# CH32F203CBT6-R0.net
KiCad netlist of a schematic drawn in Altium Designer
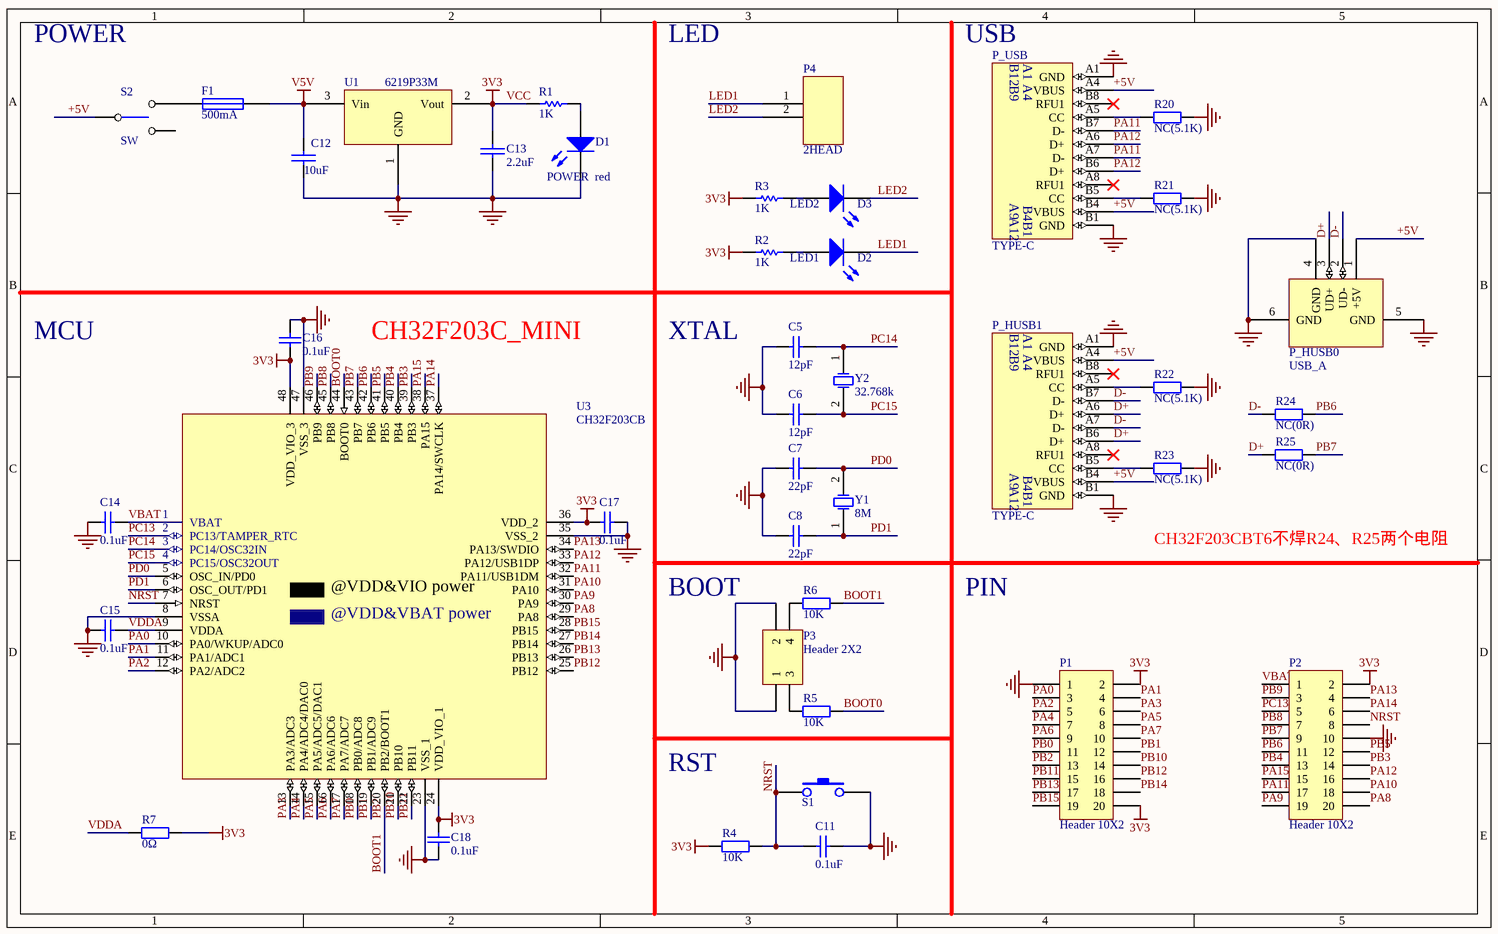
[diagram p0: CH32F203CBT6-R0.SchDoc]

(export (version "E")
  (design (tool "Eeschema 10.0.6"))
  (components
    (comp (ref "C5")
      (value "12pF")
      (footprint "0603")
      (description "Capacitor")
      (fields (field (name "PUBLISHER") "Altium Limited"))
      (libsource (lib "*") (part "Cap"))
    )
    (comp (ref "C6")
      (value "12pF")
      (footprint "0603")
      (description "Capacitor")
      (fields (field (name "PUBLISHER") "Altium Limited"))
      (libsource (lib "*") (part "Cap"))
    )
    (comp (ref "C7")
      (value "22pF")
      (footprint "0603")
      (description "Capacitor")
      (fields (field (name "PUBLISHER") "Altium Limited"))
      (libsource (lib "*") (part "Cap"))
    )
    (comp (ref "C8")
      (value "22pF")
      (footprint "0603")
      (description "Capacitor")
      (fields (field (name "PUBLISHER") "Altium Limited"))
      (libsource (lib "*") (part "Cap"))
    )
    (comp (ref "C11")
      (value "0.1uF")
      (footprint "0603")
      (description "Capacitor")
      (fields (field (name "PUBLISHER") "Altium Limited"))
      (libsource (lib "*") (part "Cap"))
    )
    (comp (ref "C12")
      (value "10uF")
      (footprint "3216")
      (description "Capacitor")
      (libsource (lib "*") (part "CAP"))
    )
    (comp (ref "C13")
      (value "2.2uF")
      (footprint "0603")
      (description "Capacitor")
      (libsource (lib "*") (part "CAP"))
    )
    (comp (ref "C14")
      (value "0.1uF")
      (footprint "0603")
      (description "Capacitor")
      (fields (field (name "PUBLISHER") "Altium Limited"))
      (libsource (lib "*") (part "Cap"))
    )
    (comp (ref "C15")
      (value "0.1uF")
      (footprint "0603")
      (description "Capacitor")
      (fields (field (name "PUBLISHER") "Altium Limited"))
      (libsource (lib "*") (part "Cap"))
    )
    (comp (ref "C16")
      (value "0.1uF")
      (footprint "0603")
      (description "Capacitor")
      (fields (field (name "PUBLISHER") "Altium Limited"))
      (libsource (lib "*") (part "Cap"))
    )
    (comp (ref "C17")
      (value "0.1uF")
      (footprint "0603")
      (description "Capacitor")
      (fields (field (name "PUBLISHER") "Altium Limited"))
      (libsource (lib "*") (part "Cap"))
    )
    (comp (ref "C18")
      (value "0.1uF")
      (footprint "0603")
      (description "Capacitor")
      (fields (field (name "PUBLISHER") "Altium Limited"))
      (libsource (lib "*") (part "Cap"))
    )
    (comp (ref "D1")
      (value "POWER  red")
      (footprint "0603L")
      (description "Typical INFRARED GaAs LED")
      (fields (field (name "PUBLISHER") "Altium Limited"))
      (libsource (lib "*") (part "LED0"))
    )
    (comp (ref "D2")
      (value "LED1")
      (footprint "0603L")
      (description "Typical INFRARED GaAs LED")
      (fields (field (name "PUBLISHER") "Altium Limited"))
      (libsource (lib "*") (part "LED0"))
    )
    (comp (ref "D3")
      (value "LED2")
      (footprint "0603L")
      (description "Typical INFRARED GaAs LED")
      (fields (field (name "PUBLISHER") "Altium Limited"))
      (libsource (lib "*") (part "LED0"))
    )
    (comp (ref "F1")
      (value "500mA")
      (footprint "0603")
      (description "Fuse")
      (libsource (lib "*") (part "FUSE1"))
    )
    (comp (ref "P1")
      (value "Header 10X2")
      (footprint "IDC20")
      (description "Header, 10-Pin, Dual row")
      (fields (field (name "PUBLISHER") "Altium Limited"))
      (libsource (lib "*") (part "Header 10X2"))
    )
    (comp (ref "P2")
      (value "Header 10X2")
      (footprint "IDC20")
      (description "Header, 10-Pin, Dual row")
      (fields (field (name "PUBLISHER") "Altium Limited"))
      (libsource (lib "*") (part "Header 10X2"))
    )
    (comp (ref "P3")
      (value "Header 2X2")
      (footprint "HDR2X2")
      (description "Header, 2-Pin, Dual row")
      (fields (field (name "PUBLISHER") "Altium Limited"))
      (libsource (lib "*") (part "Header 2X2"))
    )
    (comp (ref "P4") (value "2HEAD") (footprint "SIP2 - 40mil") (libsource (lib "*") (part "2HEAD")))
    (comp (ref "P_HUSB0")
      (value "USB_A")
      (footprint "USBA-L")
      (description "USB Port")
      (libsource (lib "*") (part "USB"))
    )
    (comp (ref "P_HUSB1")
      (value "TYPE-C")
      (footprint "TYPE-C-Receptacle-2.0")
      (libsource (lib "*") (part "TYPE-C1"))
    )
    (comp (ref "P_USB")
      (value "TYPE-C")
      (footprint "TYPE-C-Receptacle-2.0")
      (libsource (lib "*") (part "TYPE-C1"))
    )
    (comp (ref "R1")
      (value "1K")
      (footprint "0603")
      (description "Semiconductor Resistor")
      (fields (field (name "PUBLISHER") "Altium Limited"))
      (libsource (lib "*") (part "Res Semi"))
    )
    (comp (ref "R2")
      (value "1K")
      (footprint "0603")
      (description "Semiconductor Resistor")
      (fields (field (name "PUBLISHER") "Altium Limited"))
      (libsource (lib "*") (part "Res Semi"))
    )
    (comp (ref "R3")
      (value "1K")
      (footprint "0603")
      (description "Semiconductor Resistor")
      (fields (field (name "PUBLISHER") "Altium Limited"))
      (libsource (lib "*") (part "Res Semi"))
    )
    (comp (ref "R4")
      (value "10K")
      (footprint "0603")
      (description "Resistor")
      (fields (field (name "PUBLISHER") "Altium Limited"))
      (libsource (lib "*") (part "Res2"))
    )
    (comp (ref "R5")
      (value "10K")
      (footprint "0603")
      (description "Resistor")
      (fields (field (name "PUBLISHER") "Altium Limited"))
      (libsource (lib "*") (part "Res2"))
    )
    (comp (ref "R6")
      (value "10K")
      (footprint "0603")
      (description "Resistor")
      (fields (field (name "PUBLISHER") "Altium Limited"))
      (libsource (lib "*") (part "Res2"))
    )
    (comp (ref "R7")
      (value "0Ω")
      (footprint "0603")
      (description "Resistor")
      (fields (field (name "PUBLISHER") "Altium Limited"))
      (libsource (lib "*") (part "Res2"))
    )
    (comp (ref "R20")
      (value "NC(5.1K)")
      (footprint "0603")
      (description "Resistor")
      (libsource (lib "Miscellaneous Devices") (part "Res2"))
    )
    (comp (ref "R21")
      (value "NC(5.1K)")
      (footprint "0603")
      (description "Resistor")
      (libsource (lib "Miscellaneous Devices") (part "Res2"))
    )
    (comp (ref "R22")
      (value "NC(5.1K)")
      (footprint "0603")
      (description "Resistor")
      (libsource (lib "Miscellaneous Devices") (part "Res2"))
    )
    (comp (ref "R23")
      (value "NC(5.1K)")
      (footprint "0603")
      (description "Resistor")
      (libsource (lib "Miscellaneous Devices") (part "Res2"))
    )
    (comp (ref "R24")
      (value "NC(0R)")
      (footprint "0603")
      (description "Resistor")
      (libsource (lib "Miscellaneous Devices") (part "Res2"))
    )
    (comp (ref "R25")
      (value "NC(0R)")
      (footprint "0603")
      (description "Resistor")
      (libsource (lib "Miscellaneous Devices") (part "Res2"))
    )
    (comp (ref "S1") (value "KEY") (footprint "贴片按键") (libsource (lib "*") (part "KEY")))
    (comp (ref "S2") (value "SW") (footprint "KEY2") (libsource (lib "*") (part "SW")))
    (comp (ref "U1")
      (value "6219P33M")
      (footprint "SOT-23")
      (libsource (lib "wch_sch_others") (part "6219P33M"))
    )
    (comp (ref "U3")
      (value "CH32F203CB")
      (footprint "LQFP48")
      (description "ARM M3 HD-MCU, 144MHz, 8*UART, 10*Timer, 4*OPA")
      (libsource (lib "CHXXX") (part "CH32F203CB"))
    )
    (comp (ref "Y1")
      (value "8M")
      (footprint "XT62/28")
      (description "Crystal Oscillator")
      (fields (field (name "PUBLISHER") "Altium Limited"))
      (libsource (lib "*") (part "XTAL"))
    )
    (comp (ref "Y2")
      (value "32.768k")
      (footprint "FC-135")
      (description "Crystal Oscillator")
      (fields (field (name "PUBLISHER") "Altium Limited"))
      (libsource (lib "*") (part "XTAL"))
    )
  )
  (nets
    (net (code "1") (name "/+5V") (class "Default")
      (node (ref "P_HUSB0") (pin "1") (pinfunction "+5V_1") (pintype "power_in"))
      (node (ref "P_HUSB1") (pin "A4") (pinfunction "VBUS_A4") (pintype "bidirectional"))
      (node (ref "P_HUSB1") (pin "B4") (pinfunction "VBUS_B4") (pintype "bidirectional"))
      (node (ref "P_USB") (pin "A4") (pinfunction "VBUS_A4") (pintype "bidirectional"))
      (node (ref "P_USB") (pin "B4") (pinfunction "VBUS_B4") (pintype "bidirectional"))
      (node (ref "S2") (pin "1") (pinfunction "1_1") (pintype "passive"))
    )
    (net (code "3") (name "/BOOT0") (class "Default")
      (node (ref "R5") (pin "1") (pinfunction "1_1") (pintype "passive"))
      (node (ref "U3") (pin "44") (pinfunction "BOOT0_44") (pintype "input"))
    )
    (net (code "4") (name "/BOOT1") (class "Default")
      (node (ref "P1") (pin "13") (pinfunction "13_13") (pintype "passive"))
      (node (ref "R6") (pin "1") (pinfunction "1_1") (pintype "passive"))
      (node (ref "U3") (pin "20") (pinfunction "PB2/BOOT1_20") (pintype "bidirectional"))
    )
    (net (code "5") (name "/D+") (class "Default")
      (node (ref "P_HUSB0") (pin "3") (pinfunction "UD+_3") (pintype "bidirectional"))
      (node (ref "P_HUSB1") (pin "A6") (pinfunction "D+_A6") (pintype "bidirectional"))
      (node (ref "P_HUSB1") (pin "B6") (pinfunction "D+_B6") (pintype "bidirectional"))
      (node (ref "R25") (pin "1") (pinfunction "1_1") (pintype "passive"))
    )
    (net (code "6") (name "/D-") (class "Default")
      (node (ref "P_HUSB0") (pin "2") (pinfunction "UD-_2") (pintype "bidirectional"))
      (node (ref "P_HUSB1") (pin "A7") (pinfunction "D-_A7") (pintype "bidirectional"))
      (node (ref "P_HUSB1") (pin "B7") (pinfunction "D-_B7") (pintype "bidirectional"))
      (node (ref "R24") (pin "1") (pinfunction "1_1") (pintype "passive"))
    )
    (net (code "7") (name "/LED1") (class "Default")
      (node (ref "D2") (pin "2") (pinfunction "K_2") (pintype "passive"))
      (node (ref "P4") (pin "1") (pintype "passive"))
    )
    (net (code "8") (name "/LED2") (class "Default")
      (node (ref "D3") (pin "2") (pinfunction "K_2") (pintype "passive"))
      (node (ref "P4") (pin "2") (pintype "passive"))
    )
    (net (code "9") (name "/NRST") (class "Default")
      (node (ref "C11") (pin "2") (pinfunction "2_2") (pintype "passive"))
      (node (ref "P2") (pin "8") (pinfunction "8_8") (pintype "passive"))
      (node (ref "R4") (pin "1") (pinfunction "1_1") (pintype "passive"))
      (node (ref "S1") (pin "1") (pinfunction "1_1") (pintype "passive"))
      (node (ref "U3") (pin "7") (pinfunction "NRST_7") (pintype "input"))
    )
    (net (code "10") (name "/PA0") (class "Default")
      (node (ref "P1") (pin "3") (pinfunction "3_3") (pintype "passive"))
      (node (ref "U3") (pin "10") (pinfunction "PA0/WKUP/ADC0_10") (pintype "bidirectional"))
    )
    (net (code "11") (name "/PA1") (class "Default")
      (node (ref "P1") (pin "4") (pinfunction "4_4") (pintype "passive"))
      (node (ref "U3") (pin "11") (pinfunction "PA1/ADC1_11") (pintype "bidirectional"))
    )
    (net (code "12") (name "/PA2") (class "Default")
      (node (ref "P1") (pin "5") (pinfunction "5_5") (pintype "passive"))
      (node (ref "U3") (pin "12") (pinfunction "PA2/ADC2_12") (pintype "bidirectional"))
    )
    (net (code "13") (name "/PA3") (class "Default")
      (node (ref "P1") (pin "6") (pinfunction "6_6") (pintype "passive"))
      (node (ref "U3") (pin "13") (pinfunction "PA3/ADC3_13") (pintype "bidirectional"))
    )
    (net (code "14") (name "/PA4") (class "Default")
      (node (ref "P1") (pin "7") (pinfunction "7_7") (pintype "passive"))
      (node (ref "U3") (pin "14") (pinfunction "PA4/ADC4/DAC0_14") (pintype "bidirectional"))
    )
    (net (code "15") (name "/PA5") (class "Default")
      (node (ref "P1") (pin "8") (pinfunction "8_8") (pintype "passive"))
      (node (ref "U3") (pin "15") (pinfunction "PA5/ADC5/DAC1_15") (pintype "bidirectional"))
    )
    (net (code "16") (name "/PA6") (class "Default")
      (node (ref "P1") (pin "9") (pinfunction "9_9") (pintype "passive"))
      (node (ref "U3") (pin "16") (pinfunction "PA6/ADC6_16") (pintype "bidirectional"))
    )
    (net (code "17") (name "/PA7") (class "Default")
      (node (ref "P1") (pin "10") (pinfunction "10_10") (pintype "passive"))
      (node (ref "U3") (pin "17") (pinfunction "PA7/ADC7_17") (pintype "bidirectional"))
    )
    (net (code "18") (name "/PA8") (class "Default")
      (node (ref "P2") (pin "20") (pinfunction "20_20") (pintype "passive"))
      (node (ref "U3") (pin "29") (pinfunction "PA8_29") (pintype "bidirectional"))
    )
    (net (code "19") (name "/PA9") (class "Default")
      (node (ref "P2") (pin "19") (pinfunction "19_19") (pintype "passive"))
      (node (ref "U3") (pin "30") (pinfunction "PA9_30") (pintype "bidirectional"))
    )
    (net (code "20") (name "/PA10") (class "Default")
      (node (ref "P2") (pin "18") (pinfunction "18_18") (pintype "passive"))
      (node (ref "U3") (pin "31") (pinfunction "PA10_31") (pintype "bidirectional"))
    )
    (net (code "21") (name "/PA11") (class "Default")
      (node (ref "P2") (pin "17") (pinfunction "17_17") (pintype "passive"))
      (node (ref "P_USB") (pin "A7") (pinfunction "D-_A7") (pintype "bidirectional"))
      (node (ref "P_USB") (pin "B7") (pinfunction "D-_B7") (pintype "bidirectional"))
      (node (ref "U3") (pin "32") (pinfunction "PA11/USB1DM_32") (pintype "bidirectional"))
    )
    (net (code "22") (name "/PA12") (class "Default")
      (node (ref "P2") (pin "16") (pinfunction "16_16") (pintype "passive"))
      (node (ref "P_USB") (pin "A6") (pinfunction "D+_A6") (pintype "bidirectional"))
      (node (ref "P_USB") (pin "B6") (pinfunction "D+_B6") (pintype "bidirectional"))
      (node (ref "U3") (pin "33") (pinfunction "PA12/USB1DP_33") (pintype "bidirectional"))
    )
    (net (code "23") (name "/PA13") (class "Default")
      (node (ref "P2") (pin "4") (pinfunction "4_4") (pintype "passive"))
      (node (ref "U3") (pin "34") (pinfunction "PA13/SWDIO_34") (pintype "bidirectional"))
    )
    (net (code "24") (name "/PA14") (class "Default")
      (node (ref "P2") (pin "6") (pinfunction "6_6") (pintype "passive"))
      (node (ref "U3") (pin "37") (pinfunction "PA14/SWCLK_37") (pintype "bidirectional"))
    )
    (net (code "25") (name "/PA15") (class "Default")
      (node (ref "P2") (pin "15") (pinfunction "15_15") (pintype "passive"))
      (node (ref "U3") (pin "38") (pinfunction "PA15_38") (pintype "bidirectional"))
    )
    (net (code "26") (name "/PB0") (class "Default")
      (node (ref "P1") (pin "11") (pinfunction "11_11") (pintype "passive"))
      (node (ref "U3") (pin "18") (pinfunction "PB0/ADC8_18") (pintype "bidirectional"))
    )
    (net (code "27") (name "/PB1") (class "Default")
      (node (ref "P1") (pin "12") (pinfunction "12_12") (pintype "passive"))
      (node (ref "U3") (pin "19") (pinfunction "PB1/ADC9_19") (pintype "bidirectional"))
    )
    (net (code "28") (name "/PB3") (class "Default")
      (node (ref "P2") (pin "14") (pinfunction "14_14") (pintype "passive"))
      (node (ref "U3") (pin "39") (pinfunction "PB3_39") (pintype "bidirectional"))
    )
    (net (code "29") (name "/PB4") (class "Default")
      (node (ref "P2") (pin "13") (pinfunction "13_13") (pintype "passive"))
      (node (ref "U3") (pin "40") (pinfunction "PB4_40") (pintype "bidirectional"))
    )
    (net (code "30") (name "/PB5") (class "Default")
      (node (ref "P2") (pin "12") (pinfunction "12_12") (pintype "passive"))
      (node (ref "U3") (pin "41") (pinfunction "PB5_41") (pintype "bidirectional"))
    )
    (net (code "31") (name "/PB6") (class "Default")
      (node (ref "P2") (pin "11") (pinfunction "11_11") (pintype "passive"))
      (node (ref "R24") (pin "2") (pinfunction "2_2") (pintype "passive"))
      (node (ref "U3") (pin "42") (pinfunction "PB6_42") (pintype "bidirectional"))
    )
    (net (code "32") (name "/PB7") (class "Default")
      (node (ref "P2") (pin "9") (pinfunction "9_9") (pintype "passive"))
      (node (ref "R25") (pin "2") (pinfunction "2_2") (pintype "passive"))
      (node (ref "U3") (pin "43") (pinfunction "PB7_43") (pintype "bidirectional"))
    )
    (net (code "33") (name "/PB8") (class "Default")
      (node (ref "P2") (pin "7") (pinfunction "7_7") (pintype "passive"))
      (node (ref "U3") (pin "45") (pinfunction "PB8_45") (pintype "bidirectional"))
    )
    (net (code "34") (name "/PB9") (class "Default")
      (node (ref "P2") (pin "3") (pinfunction "3_3") (pintype "passive"))
      (node (ref "U3") (pin "46") (pinfunction "PB9_46") (pintype "bidirectional"))
    )
    (net (code "35") (name "/PB10") (class "Default")
      (node (ref "P1") (pin "14") (pinfunction "14_14") (pintype "passive"))
      (node (ref "U3") (pin "21") (pinfunction "PB10_21") (pintype "bidirectional"))
    )
    (net (code "36") (name "/PB11") (class "Default")
      (node (ref "P1") (pin "15") (pinfunction "15_15") (pintype "passive"))
      (node (ref "U3") (pin "22") (pinfunction "PB11_22") (pintype "bidirectional"))
    )
    (net (code "37") (name "/PB12") (class "Default")
      (node (ref "P1") (pin "16") (pinfunction "16_16") (pintype "passive"))
      (node (ref "U3") (pin "25") (pinfunction "PB12_25") (pintype "bidirectional"))
    )
    (net (code "38") (name "/PB13") (class "Default")
      (node (ref "P1") (pin "17") (pinfunction "17_17") (pintype "passive"))
      (node (ref "U3") (pin "26") (pinfunction "PB13_26") (pintype "bidirectional"))
    )
    (net (code "39") (name "/PB14") (class "Default")
      (node (ref "P1") (pin "18") (pinfunction "18_18") (pintype "passive"))
      (node (ref "U3") (pin "27") (pinfunction "PB14_27") (pintype "bidirectional"))
    )
    (net (code "40") (name "/PB15") (class "Default")
      (node (ref "P1") (pin "19") (pinfunction "19_19") (pintype "passive"))
      (node (ref "U3") (pin "28") (pinfunction "PB15_28") (pintype "bidirectional"))
    )
    (net (code "41") (name "/PC13") (class "Default")
      (node (ref "P2") (pin "5") (pinfunction "5_5") (pintype "passive"))
      (node (ref "U3") (pin "2") (pinfunction "PC13/TAMPER_RTC_2") (pintype "bidirectional"))
    )
    (net (code "42") (name "/PC14") (class "Default")
      (node (ref "C5") (pin "1") (pinfunction "1_1") (pintype "passive"))
      (node (ref "U3") (pin "3") (pinfunction "PC14/OSC32IN_3") (pintype "bidirectional"))
      (node (ref "Y2") (pin "1") (pinfunction "OSC1_1") (pintype "passive"))
    )
    (net (code "43") (name "/PC15") (class "Default")
      (node (ref "C6") (pin "1") (pinfunction "1_1") (pintype "passive"))
      (node (ref "U3") (pin "4") (pinfunction "PC15/OSC32OUT_4") (pintype "bidirectional"))
      (node (ref "Y2") (pin "2") (pinfunction "OSC2_2") (pintype "passive"))
    )
    (net (code "44") (name "/PD0") (class "Default")
      (node (ref "C7") (pin "2") (pinfunction "2_2") (pintype "passive"))
      (node (ref "U3") (pin "5") (pinfunction "OSC_IN/PD0_5") (pintype "bidirectional"))
      (node (ref "Y1") (pin "2") (pinfunction "OSC2_2") (pintype "passive"))
    )
    (net (code "45") (name "/PD1") (class "Default")
      (node (ref "C8") (pin "2") (pinfunction "2_2") (pintype "passive"))
      (node (ref "U3") (pin "6") (pinfunction "OSC_OUT/PD1_6") (pintype "bidirectional"))
      (node (ref "Y1") (pin "1") (pinfunction "OSC1_1") (pintype "passive"))
    )
    (net (code "46") (name "/VBAT") (class "Default")
      (node (ref "C14") (pin "1") (pinfunction "1_1") (pintype "passive"))
      (node (ref "P2") (pin "1") (pinfunction "1_1") (pintype "passive"))
      (node (ref "U3") (pin "1") (pinfunction "VBAT_1") (pintype "power_in"))
    )
    (net (code "47") (name "/VDDA") (class "Default")
      (node (ref "C15") (pin "1") (pinfunction "1_1") (pintype "passive"))
      (node (ref "R7") (pin "2") (pinfunction "2_2") (pintype "passive"))
      (node (ref "U3") (pin "9") (pinfunction "VDDA_9") (pintype "power_in"))
    )
    (net (code "48") (name "3V3") (class "Default")
      (node (ref "C13") (pin "1") (pinfunction "1_1") (pintype "passive"))
      (node (ref "C16") (pin "2") (pinfunction "2_2") (pintype "passive"))
      (node (ref "C17") (pin "2") (pinfunction "2_2") (pintype "passive"))
      (node (ref "C18") (pin "2") (pinfunction "2_2") (pintype "passive"))
      (node (ref "P1") (pin "2") (pinfunction "2_2") (pintype "passive"))
      (node (ref "P1") (pin "20") (pinfunction "20_20") (pintype "passive"))
      (node (ref "P2") (pin "2") (pinfunction "2_2") (pintype "passive"))
      (node (ref "R1") (pin "2") (pinfunction "2_2") (pintype "passive"))
      (node (ref "R2") (pin "1") (pinfunction "1_1") (pintype "passive"))
      (node (ref "R3") (pin "1") (pinfunction "1_1") (pintype "passive"))
      (node (ref "R4") (pin "2") (pinfunction "2_2") (pintype "passive"))
      (node (ref "R7") (pin "1") (pinfunction "1_1") (pintype "passive"))
      (node (ref "U1") (pin "2") (pinfunction "Vout_2") (pintype "passive"))
      (node (ref "U3") (pin "24") (pinfunction "VDD_VIO_1_24") (pintype "power_in"))
      (node (ref "U3") (pin "36") (pinfunction "VDD_2_36") (pintype "power_in"))
      (node (ref "U3") (pin "48") (pinfunction "VDD_VIO_3_48") (pintype "power_in"))
    )
    (net (code "49") (name "GND") (class "Default")
      (node (ref "C11") (pin "1") (pinfunction "1_1") (pintype "passive"))
      (node (ref "C12") (pin "2") (pinfunction "2_2") (pintype "passive"))
      (node (ref "C13") (pin "2") (pinfunction "2_2") (pintype "passive"))
      (node (ref "C14") (pin "2") (pinfunction "2_2") (pintype "passive"))
      (node (ref "C15") (pin "2") (pinfunction "2_2") (pintype "passive"))
      (node (ref "C16") (pin "1") (pinfunction "1_1") (pintype "passive"))
      (node (ref "C17") (pin "1") (pinfunction "1_1") (pintype "passive"))
      (node (ref "C18") (pin "1") (pinfunction "1_1") (pintype "passive"))
      (node (ref "C5") (pin "2") (pinfunction "2_2") (pintype "passive"))
      (node (ref "C6") (pin "2") (pinfunction "2_2") (pintype "passive"))
      (node (ref "C7") (pin "1") (pinfunction "1_1") (pintype "passive"))
      (node (ref "C8") (pin "1") (pinfunction "1_1") (pintype "passive"))
      (node (ref "D1") (pin "2") (pinfunction "K_2") (pintype "passive"))
      (node (ref "P1") (pin "1") (pinfunction "1_1") (pintype "passive"))
      (node (ref "P2") (pin "10") (pinfunction "10_10") (pintype "passive"))
      (node (ref "P3") (pin "1") (pinfunction "1_1") (pintype "passive"))
      (node (ref "P3") (pin "2") (pinfunction "2_2") (pintype "passive"))
      (node (ref "P_HUSB0") (pin "4") (pinfunction "GND_4") (pintype "power_in"))
      (node (ref "P_HUSB0") (pin "5") (pinfunction "GND_5") (pintype "power_in"))
      (node (ref "P_HUSB0") (pin "6") (pinfunction "GND_6") (pintype "power_in"))
      (node (ref "P_HUSB1") (pin "A1") (pinfunction "GND_A1") (pintype "bidirectional"))
      (node (ref "P_HUSB1") (pin "B1") (pinfunction "GND_B1") (pintype "bidirectional"))
      (node (ref "P_USB") (pin "A1") (pinfunction "GND_A1") (pintype "bidirectional"))
      (node (ref "P_USB") (pin "B1") (pinfunction "GND_B1") (pintype "bidirectional"))
      (node (ref "R20") (pin "2") (pinfunction "2_2") (pintype "passive"))
      (node (ref "R21") (pin "2") (pinfunction "2_2") (pintype "passive"))
      (node (ref "R22") (pin "2") (pinfunction "2_2") (pintype "passive"))
      (node (ref "R23") (pin "2") (pinfunction "2_2") (pintype "passive"))
      (node (ref "S1") (pin "3") (pinfunction "3_3") (pintype "passive"))
      (node (ref "U1") (pin "1") (pinfunction "GND_1") (pintype "passive"))
      (node (ref "U3") (pin "23") (pinfunction "VSS_1_23") (pintype "power_in"))
      (node (ref "U3") (pin "35") (pinfunction "VSS_2_35") (pintype "power_in"))
      (node (ref "U3") (pin "47") (pinfunction "VSS_3_47") (pintype "power_in"))
      (node (ref "U3") (pin "8") (pinfunction "VSSA_8") (pintype "power_in"))
    )
    (net (code "50") (name "Net-(D1-A)") (class "Default")
      (node (ref "D1") (pin "1") (pinfunction "A_1") (pintype "passive"))
      (node (ref "R1") (pin "1") (pinfunction "1_1") (pintype "passive"))
    )
    (net (code "51") (name "Net-(D2-A)") (class "Default")
      (node (ref "D2") (pin "1") (pinfunction "A_1") (pintype "passive"))
      (node (ref "R2") (pin "2") (pinfunction "2_2") (pintype "passive"))
    )
    (net (code "52") (name "Net-(D3-A)") (class "Default")
      (node (ref "D3") (pin "1") (pinfunction "A_1") (pintype "passive"))
      (node (ref "R3") (pin "2") (pinfunction "2_2") (pintype "passive"))
    )
    (net (code "53") (name "Net-(F1-Pad1)") (class "Default")
      (node (ref "F1") (pin "1") (pinfunction "1_1") (pintype "passive"))
      (node (ref "S2") (pin "3") (pinfunction "3_3") (pintype "passive"))
    )
    (net (code "54") (name "Net-(P3-Pad3)") (class "Default")
      (node (ref "P3") (pin "3") (pinfunction "3_3") (pintype "passive"))
      (node (ref "R5") (pin "2") (pinfunction "2_2") (pintype "passive"))
    )
    (net (code "55") (name "Net-(P3-Pad4)") (class "Default")
      (node (ref "P3") (pin "4") (pinfunction "4_4") (pintype "passive"))
      (node (ref "R6") (pin "2") (pinfunction "2_2") (pintype "passive"))
    )
    (net (code "56") (name "Net-(P_HUSB1-CC-PadA5)") (class "Default")
      (node (ref "P_HUSB1") (pin "A5") (pinfunction "CC_A5") (pintype "bidirectional"))
      (node (ref "R22") (pin "1") (pinfunction "1_1") (pintype "passive"))
    )
    (net (code "57") (name "Net-(P_HUSB1-CC-PadB5)") (class "Default")
      (node (ref "P_HUSB1") (pin "B5") (pinfunction "CC_B5") (pintype "bidirectional"))
      (node (ref "R23") (pin "1") (pinfunction "1_1") (pintype "passive"))
    )
    (net (code "58") (name "Net-(P_USB-CC-PadA5)") (class "Default")
      (node (ref "P_USB") (pin "A5") (pinfunction "CC_A5") (pintype "bidirectional"))
      (node (ref "R20") (pin "1") (pinfunction "1_1") (pintype "passive"))
    )
    (net (code "59") (name "Net-(P_USB-CC-PadB5)") (class "Default")
      (node (ref "P_USB") (pin "B5") (pinfunction "CC_B5") (pintype "bidirectional"))
      (node (ref "R21") (pin "1") (pinfunction "1_1") (pintype "passive"))
    )
    (net (code "60") (name "V5V") (class "Default")
      (node (ref "C12") (pin "1") (pinfunction "1_1") (pintype "passive"))
      (node (ref "F1") (pin "2") (pinfunction "2_2") (pintype "passive"))
      (node (ref "U1") (pin "3") (pinfunction "Vin_3") (pintype "passive"))
    )
    (net (code "61") (name "unconnected-(P_HUSB1-RFU1-PadA8)") (class "Default")
      (node (ref "P_HUSB1") (pin "A8") (pinfunction "RFU1_A8") (pintype "bidirectional+no_connect"))
    )
    (net (code "62") (name "unconnected-(P_HUSB1-RFU1-PadB8)") (class "Default")
      (node (ref "P_HUSB1") (pin "B8") (pinfunction "RFU1_B8") (pintype "bidirectional+no_connect"))
    )
    (net (code "63") (name "unconnected-(P_USB-RFU1-PadA8)") (class "Default")
      (node (ref "P_USB") (pin "A8") (pinfunction "RFU1_A8") (pintype "bidirectional+no_connect"))
    )
    (net (code "64") (name "unconnected-(P_USB-RFU1-PadB8)") (class "Default")
      (node (ref "P_USB") (pin "B8") (pinfunction "RFU1_B8") (pintype "bidirectional+no_connect"))
    )
    (net (code "65") (name "unconnected-(S2-Pad2)") (class "Default")
      (node (ref "S2") (pin "2") (pinfunction "2_2") (pintype "passive"))
    )
  )
)
